# FrontEnd-rev1-superseded.net
KiCad netlist of a schematic drawn in Altium Designer
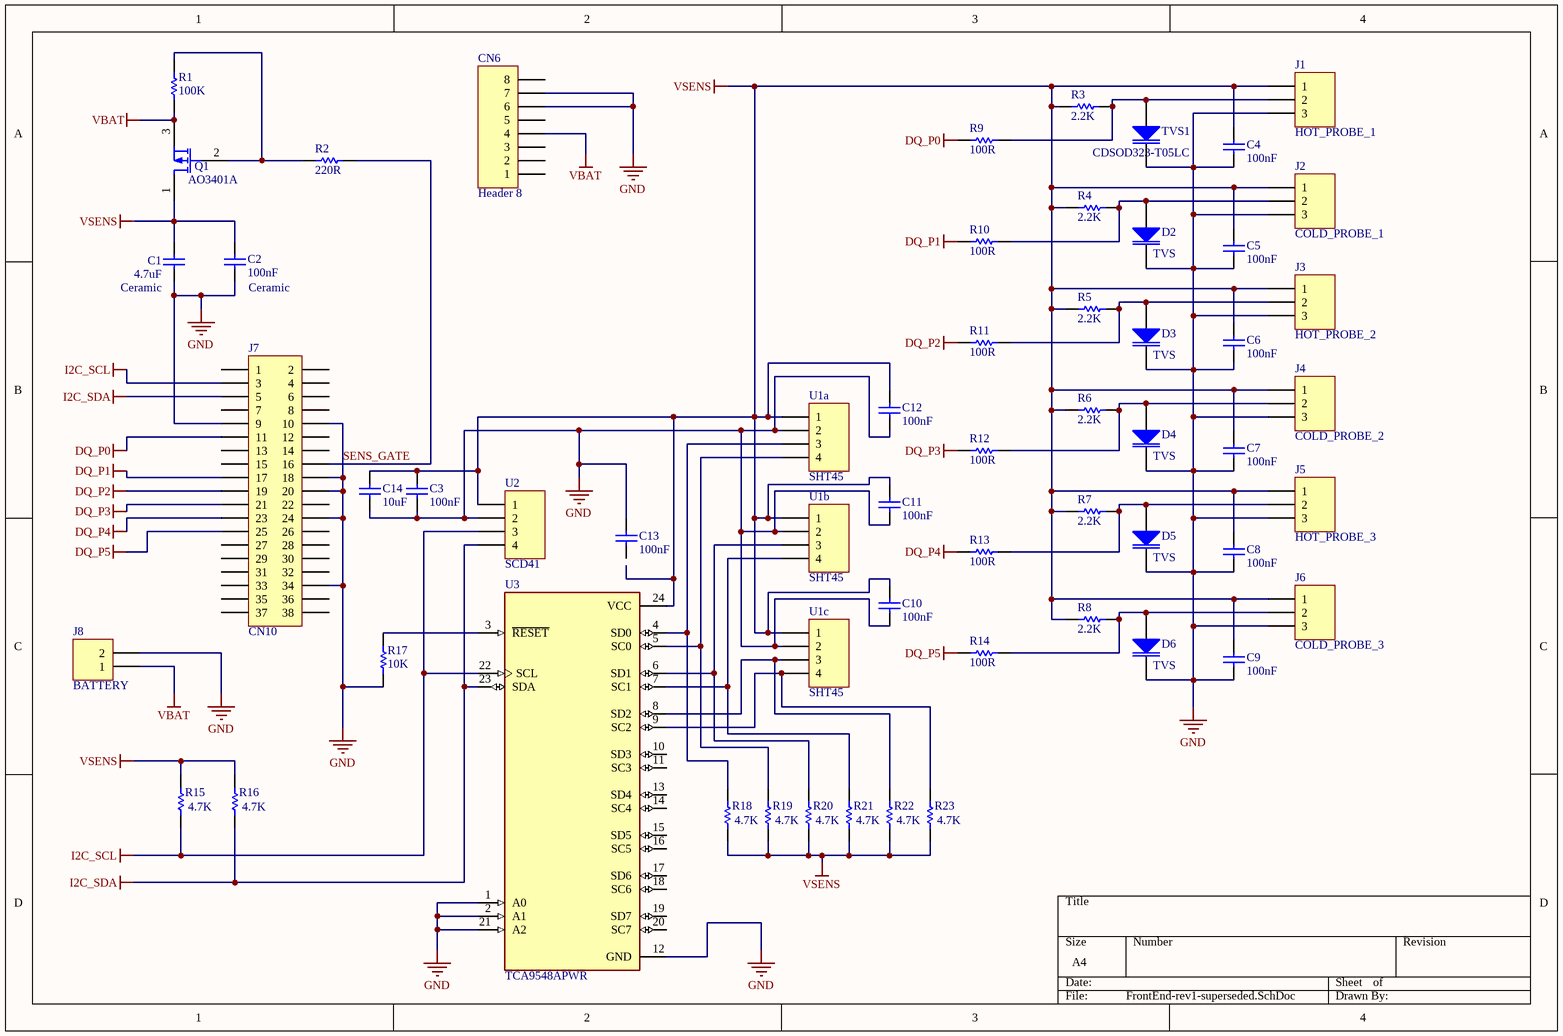
[diagram p0: FrontEnd-rev1-superseded.SchDoc]

(export (version "E")
  (design (tool "Eeschema 10.0.6"))
  (components
    (comp (ref "C1")
      (value "Ceramic")
      (footprint "RAD-0.3")
      (description "Capacitor")
      (fields (field (name "ALTIUM_VALUE") "4.7uF") (field (name "PUBLISHER") "Altium Limited"))
      (libsource (lib "Miscellaneous Devices") (part "Cap"))
    )
    (comp (ref "C2")
      (value "Ceramic")
      (footprint "RAD-0.3")
      (description "Capacitor")
      (fields (field (name "ALTIUM_VALUE") "100nF") (field (name "PUBLISHER") "Altium Limited"))
      (libsource (lib "Miscellaneous Devices") (part "Cap"))
    )
    (comp (ref "C3")
      (value "100nF")
      (footprint "RAD-0.3")
      (description "Capacitor")
      (fields (field (name "PUBLISHER") "Altium Limited"))
      (libsource (lib "Miscellaneous Devices") (part "Cap"))
    )
    (comp (ref "C4")
      (value "100nF")
      (footprint "RAD-0.3")
      (description "Capacitor")
      (fields (field (name "PUBLISHER") "Altium Limited"))
      (libsource (lib "Miscellaneous Devices") (part "Cap"))
    )
    (comp (ref "C5")
      (value "100nF")
      (footprint "RAD-0.3")
      (description "Capacitor")
      (fields (field (name "PUBLISHER") "Altium Limited"))
      (libsource (lib "Miscellaneous Devices") (part "Cap"))
    )
    (comp (ref "C6")
      (value "100nF")
      (footprint "RAD-0.3")
      (description "Capacitor")
      (fields (field (name "PUBLISHER") "Altium Limited"))
      (libsource (lib "Miscellaneous Devices") (part "Cap"))
    )
    (comp (ref "C7")
      (value "100nF")
      (footprint "RAD-0.3")
      (description "Capacitor")
      (fields (field (name "PUBLISHER") "Altium Limited"))
      (libsource (lib "Miscellaneous Devices") (part "Cap"))
    )
    (comp (ref "C8")
      (value "100nF")
      (footprint "RAD-0.3")
      (description "Capacitor")
      (fields (field (name "PUBLISHER") "Altium Limited"))
      (libsource (lib "Miscellaneous Devices") (part "Cap"))
    )
    (comp (ref "C9")
      (value "100nF")
      (footprint "RAD-0.3")
      (description "Capacitor")
      (fields (field (name "PUBLISHER") "Altium Limited"))
      (libsource (lib "Miscellaneous Devices") (part "Cap"))
    )
    (comp (ref "C10")
      (value "100nF")
      (footprint "RAD-0.3")
      (description "Capacitor")
      (fields (field (name "PUBLISHER") "Altium Limited"))
      (libsource (lib "Miscellaneous Devices") (part "Cap"))
    )
    (comp (ref "C11")
      (value "100nF")
      (footprint "RAD-0.3")
      (description "Capacitor")
      (fields (field (name "PUBLISHER") "Altium Limited"))
      (libsource (lib "Miscellaneous Devices") (part "Cap"))
    )
    (comp (ref "C12")
      (value "100nF")
      (footprint "RAD-0.3")
      (description "Capacitor")
      (fields (field (name "PUBLISHER") "Altium Limited"))
      (libsource (lib "Miscellaneous Devices") (part "Cap"))
    )
    (comp (ref "C13")
      (value "100nF")
      (footprint "RAD-0.3")
      (description "Capacitor")
      (fields (field (name "PUBLISHER") "Altium Limited"))
      (libsource (lib "Miscellaneous Devices") (part "Cap"))
    )
    (comp (ref "C14")
      (value "10uF")
      (footprint "RAD-0.3")
      (description "Capacitor")
      (fields (field (name "Comment") "100nF") (field (name "PUBLISHER") "Altium Limited"))
      (libsource (lib "Miscellaneous Devices") (part "Cap"))
    )
    (comp (ref "CN6")
      (value "Header 8")
      (footprint "HDR1X8")
      (description "Header, 8-Pin")
      (fields (field (name "PUBLISHER") "Altium Limited"))
      (libsource (lib "Miscellaneous Connectors") (part "Header 8"))
    )
    (comp (ref "D2")
      (value "TVS")
      (footprint "SOT23_N")
      (description "SOT23 Silicon Planar Variable Capacitance Diode")
      (fields (field (name "PUBLISHER") "Altium Limited"))
      (libsource (lib "Miscellaneous Devices") (part "Diode BBY40"))
    )
    (comp (ref "D3")
      (value "TVS")
      (footprint "SOT23_N")
      (description "SOT23 Silicon Planar Variable Capacitance Diode")
      (fields (field (name "PUBLISHER") "Altium Limited"))
      (libsource (lib "Miscellaneous Devices") (part "Diode BBY40"))
    )
    (comp (ref "D4")
      (value "TVS")
      (footprint "SOT23_N")
      (description "SOT23 Silicon Planar Variable Capacitance Diode")
      (fields (field (name "PUBLISHER") "Altium Limited"))
      (libsource (lib "Miscellaneous Devices") (part "Diode BBY40"))
    )
    (comp (ref "D5")
      (value "TVS")
      (footprint "SOT23_N")
      (description "SOT23 Silicon Planar Variable Capacitance Diode")
      (fields (field (name "PUBLISHER") "Altium Limited"))
      (libsource (lib "Miscellaneous Devices") (part "Diode BBY40"))
    )
    (comp (ref "D6")
      (value "TVS")
      (footprint "SOT23_N")
      (description "SOT23 Silicon Planar Variable Capacitance Diode")
      (fields (field (name "PUBLISHER") "Altium Limited"))
      (libsource (lib "Miscellaneous Devices") (part "Diode BBY40"))
    )
    (comp (ref "J1")
      (value "HOT_PROBE_1")
      (footprint "HDR1X3")
      (description "Header, 3-Pin")
      (fields (field (name "PUBLISHER") "Altium Limited"))
      (libsource (lib "Miscellaneous Connectors") (part "Header 3"))
    )
    (comp (ref "J2")
      (value "COLD_PROBE_1")
      (footprint "HDR1X3")
      (description "Header, 3-Pin")
      (fields (field (name "PUBLISHER") "Altium Limited"))
      (libsource (lib "Miscellaneous Connectors") (part "Header 3"))
    )
    (comp (ref "J3")
      (value "HOT_PROBE_2")
      (footprint "HDR1X3")
      (description "Header, 3-Pin")
      (fields (field (name "PUBLISHER") "Altium Limited"))
      (libsource (lib "Miscellaneous Connectors") (part "Header 3"))
    )
    (comp (ref "J4")
      (value "COLD_PROBE_2")
      (footprint "HDR1X3")
      (description "Header, 3-Pin")
      (fields (field (name "PUBLISHER") "Altium Limited"))
      (libsource (lib "Miscellaneous Connectors") (part "Header 3"))
    )
    (comp (ref "J5")
      (value "HOT_PROBE_3")
      (footprint "HDR1X3")
      (description "Header, 3-Pin")
      (fields (field (name "PUBLISHER") "Altium Limited"))
      (libsource (lib "Miscellaneous Connectors") (part "Header 3"))
    )
    (comp (ref "J6")
      (value "COLD_PROBE_3")
      (footprint "HDR1X3")
      (description "Header, 3-Pin")
      (fields (field (name "PUBLISHER") "Altium Limited"))
      (libsource (lib "Miscellaneous Connectors") (part "Header 3"))
    )
    (comp (ref "J7")
      (value "CN10")
      (footprint "HDR2X19")
      (description "Header, 19-Pin, Dual row")
      (fields (field (name "PUBLISHER") "Altium Limited"))
      (libsource (lib "Miscellaneous Connectors") (part "Header 19X2"))
    )
    (comp (ref "J8")
      (value "BATTERY")
      (footprint "HDR1X2")
      (description "Header, 2-Pin")
      (fields (field (name "PUBLISHER") "Altium Limited"))
      (libsource (lib "Miscellaneous Connectors") (part "Header 2"))
    )
    (comp (ref "Q1")
      (value "AO3401A")
      (footprint "E3")
      (description "P-Channel MOSFET")
      (fields (field (name "PUBLISHER") "Altium Limited"))
      (libsource (lib "Miscellaneous Devices") (part "MOSFET-P"))
    )
    (comp (ref "R1")
      (value "100K")
      (footprint "AXIAL-0.3")
      (description "Resistor")
      (fields (field (name "PUBLISHER") "Altium Limited"))
      (libsource (lib "Miscellaneous Devices") (part "Res1"))
    )
    (comp (ref "R2")
      (value "220R")
      (footprint "AXIAL-0.3")
      (description "Resistor")
      (fields (field (name "PUBLISHER") "Altium Limited"))
      (libsource (lib "Miscellaneous Devices") (part "Res1"))
    )
    (comp (ref "R3")
      (value "2.2K")
      (footprint "AXIAL-0.3")
      (description "Resistor")
      (fields (field (name "Comment") "pullup") (field (name "PUBLISHER") "Altium Limited"))
      (libsource (lib "Miscellaneous Devices") (part "Res1"))
    )
    (comp (ref "R4")
      (value "2.2K")
      (footprint "AXIAL-0.3")
      (description "Resistor")
      (fields (field (name "Comment") "pullup") (field (name "PUBLISHER") "Altium Limited"))
      (libsource (lib "Miscellaneous Devices") (part "Res1"))
    )
    (comp (ref "R5")
      (value "2.2K")
      (footprint "AXIAL-0.3")
      (description "Resistor")
      (fields (field (name "Comment") "pullup") (field (name "PUBLISHER") "Altium Limited"))
      (libsource (lib "Miscellaneous Devices") (part "Res1"))
    )
    (comp (ref "R6")
      (value "2.2K")
      (footprint "AXIAL-0.3")
      (description "Resistor")
      (fields (field (name "Comment") "pullup") (field (name "PUBLISHER") "Altium Limited"))
      (libsource (lib "Miscellaneous Devices") (part "Res1"))
    )
    (comp (ref "R7")
      (value "2.2K")
      (footprint "AXIAL-0.3")
      (description "Resistor")
      (fields (field (name "Comment") "pullup") (field (name "PUBLISHER") "Altium Limited"))
      (libsource (lib "Miscellaneous Devices") (part "Res1"))
    )
    (comp (ref "R8")
      (value "2.2K")
      (footprint "AXIAL-0.3")
      (description "Resistor")
      (fields (field (name "Comment") "pullup") (field (name "PUBLISHER") "Altium Limited"))
      (libsource (lib "Miscellaneous Devices") (part "Res1"))
    )
    (comp (ref "R9")
      (value "100R")
      (footprint "AXIAL-0.3")
      (description "Resistor")
      (fields (field (name "PUBLISHER") "Altium Limited"))
      (libsource (lib "Miscellaneous Devices") (part "Res1"))
    )
    (comp (ref "R10")
      (value "100R")
      (footprint "AXIAL-0.3")
      (description "Resistor")
      (fields (field (name "PUBLISHER") "Altium Limited"))
      (libsource (lib "Miscellaneous Devices") (part "Res1"))
    )
    (comp (ref "R11")
      (value "100R")
      (footprint "AXIAL-0.3")
      (description "Resistor")
      (fields (field (name "PUBLISHER") "Altium Limited"))
      (libsource (lib "Miscellaneous Devices") (part "Res1"))
    )
    (comp (ref "R12")
      (value "100R")
      (footprint "AXIAL-0.3")
      (description "Resistor")
      (fields (field (name "PUBLISHER") "Altium Limited"))
      (libsource (lib "Miscellaneous Devices") (part "Res1"))
    )
    (comp (ref "R13")
      (value "100R")
      (footprint "AXIAL-0.3")
      (description "Resistor")
      (fields (field (name "PUBLISHER") "Altium Limited"))
      (libsource (lib "Miscellaneous Devices") (part "Res1"))
    )
    (comp (ref "R14")
      (value "100R")
      (footprint "AXIAL-0.3")
      (description "Resistor")
      (fields (field (name "PUBLISHER") "Altium Limited"))
      (libsource (lib "Miscellaneous Devices") (part "Res1"))
    )
    (comp (ref "R15")
      (value "4.7K")
      (footprint "AXIAL-0.3")
      (description "Resistor")
      (fields (field (name "Comment") "pullup") (field (name "PUBLISHER") "Altium Limited"))
      (libsource (lib "Miscellaneous Devices") (part "Res1"))
    )
    (comp (ref "R16")
      (value "4.7K")
      (footprint "AXIAL-0.3")
      (description "Resistor")
      (fields (field (name "Comment") "pullup") (field (name "PUBLISHER") "Altium Limited"))
      (libsource (lib "Miscellaneous Devices") (part "Res1"))
    )
    (comp (ref "R17")
      (value "10K")
      (footprint "AXIAL-0.3")
      (description "Resistor")
      (fields (field (name "Comment") "220R") (field (name "PUBLISHER") "Altium Limited"))
      (libsource (lib "Miscellaneous Devices") (part "Res1"))
    )
    (comp (ref "R18")
      (value "4.7K")
      (footprint "AXIAL-0.3")
      (description "Resistor")
      (fields (field (name "Comment") "pullup") (field (name "PUBLISHER") "Altium Limited"))
      (libsource (lib "Miscellaneous Devices") (part "Res1"))
    )
    (comp (ref "R19")
      (value "4.7K")
      (footprint "AXIAL-0.3")
      (description "Resistor")
      (fields (field (name "Comment") "pullup") (field (name "PUBLISHER") "Altium Limited"))
      (libsource (lib "Miscellaneous Devices") (part "Res1"))
    )
    (comp (ref "R20")
      (value "4.7K")
      (footprint "AXIAL-0.3")
      (description "Resistor")
      (fields (field (name "Comment") "pullup") (field (name "PUBLISHER") "Altium Limited"))
      (libsource (lib "Miscellaneous Devices") (part "Res1"))
    )
    (comp (ref "R21")
      (value "4.7K")
      (footprint "AXIAL-0.3")
      (description "Resistor")
      (fields (field (name "Comment") "pullup") (field (name "PUBLISHER") "Altium Limited"))
      (libsource (lib "Miscellaneous Devices") (part "Res1"))
    )
    (comp (ref "R22")
      (value "4.7K")
      (footprint "AXIAL-0.3")
      (description "Resistor")
      (fields (field (name "Comment") "pullup") (field (name "PUBLISHER") "Altium Limited"))
      (libsource (lib "Miscellaneous Devices") (part "Res1"))
    )
    (comp (ref "R23")
      (value "4.7K")
      (footprint "AXIAL-0.3")
      (description "Resistor")
      (fields (field (name "Comment") "pullup") (field (name "PUBLISHER") "Altium Limited"))
      (libsource (lib "Miscellaneous Devices") (part "Res1"))
    )
    (comp (ref "TVS1")
      (value "CDSOD323-T05LC")
      (footprint "SOT23_N")
      (description "SOT23 Silicon Planar Variable Capacitance Diode")
      (fields (field (name "PUBLISHER") "Altium Limited"))
      (libsource (lib "Miscellaneous Devices") (part "Diode BBY40"))
    )
    (comp (ref "U1a")
      (value "SHT45")
      (footprint "HDR1X4")
      (description "Header, 4-Pin")
      (fields (field (name "PUBLISHER") "Altium Limited"))
      (libsource (lib "Miscellaneous Connectors") (part "Header 4"))
    )
    (comp (ref "U1b")
      (value "SHT45")
      (footprint "HDR1X4")
      (description "Header, 4-Pin")
      (fields (field (name "PUBLISHER") "Altium Limited"))
      (libsource (lib "Miscellaneous Connectors") (part "Header 4"))
    )
    (comp (ref "U1c")
      (value "SHT45")
      (footprint "HDR1X4")
      (description "Header, 4-Pin")
      (fields (field (name "PUBLISHER") "Altium Limited"))
      (libsource (lib "Miscellaneous Connectors") (part "Header 4"))
    )
    (comp (ref "U2")
      (value "SCD41")
      (footprint "HDR1X4")
      (description "Header, 4-Pin")
      (fields (field (name "PUBLISHER") "Altium Limited"))
      (libsource (lib "Miscellaneous Connectors") (part "Header 4"))
    )
    (comp (ref "U3")
      (value "TCA9548APWR")
      (footprint "SOP65P640X120-24N")
      (description "8-channel 1.65- to 5.5-V I2C/SMBus switch with reset & voltage translation")
      (fields (field (name "MF") "Texas Instruments"))
      (libsource (lib "TCA9548APWR") (part "TCA9548APWR"))
    )
  )
  (nets
    (net (code "1") (name "DQ_P0") (class "Default")
      (node (ref "J7") (pin "11") (pinfunction "11_11") (pintype "passive"))
      (node (ref "R9") (pin "1") (pinfunction "1_1") (pintype "passive"))
    )
    (net (code "2") (name "DQ_P1") (class "Default")
      (node (ref "J7") (pin "17") (pinfunction "17_17") (pintype "passive"))
      (node (ref "R10") (pin "1") (pinfunction "1_1") (pintype "passive"))
    )
    (net (code "3") (name "DQ_P2") (class "Default")
      (node (ref "J7") (pin "19") (pinfunction "19_19") (pintype "passive"))
      (node (ref "R11") (pin "1") (pinfunction "1_1") (pintype "passive"))
    )
    (net (code "4") (name "DQ_P3") (class "Default")
      (node (ref "J7") (pin "21") (pinfunction "21_21") (pintype "passive"))
      (node (ref "R12") (pin "1") (pinfunction "1_1") (pintype "passive"))
    )
    (net (code "5") (name "DQ_P4") (class "Default")
      (node (ref "J7") (pin "23") (pinfunction "23_23") (pintype "passive"))
      (node (ref "R13") (pin "1") (pinfunction "1_1") (pintype "passive"))
    )
    (net (code "6") (name "DQ_P5") (class "Default")
      (node (ref "J7") (pin "25") (pinfunction "25_25") (pintype "passive"))
      (node (ref "R14") (pin "1") (pinfunction "1_1") (pintype "passive"))
    )
    (net (code "7") (name "GND") (class "Default")
      (node (ref "C1") (pin "2") (pinfunction "2_2") (pintype "passive"))
      (node (ref "C10") (pin "2") (pinfunction "2_2") (pintype "passive"))
      (node (ref "C11") (pin "2") (pinfunction "2_2") (pintype "passive"))
      (node (ref "C12") (pin "2") (pinfunction "2_2") (pintype "passive"))
      (node (ref "C13") (pin "1") (pinfunction "1_1") (pintype "passive"))
      (node (ref "C14") (pin "2") (pinfunction "2_2") (pintype "passive"))
      (node (ref "C2") (pin "2") (pinfunction "2_2") (pintype "passive"))
      (node (ref "C3") (pin "2") (pinfunction "2_2") (pintype "passive"))
      (node (ref "C4") (pin "2") (pinfunction "2_2") (pintype "passive"))
      (node (ref "C5") (pin "2") (pinfunction "2_2") (pintype "passive"))
      (node (ref "C6") (pin "2") (pinfunction "2_2") (pintype "passive"))
      (node (ref "C7") (pin "2") (pinfunction "2_2") (pintype "passive"))
      (node (ref "C8") (pin "2") (pinfunction "2_2") (pintype "passive"))
      (node (ref "C9") (pin "2") (pinfunction "2_2") (pintype "passive"))
      (node (ref "CN6") (pin "6") (pinfunction "6_6") (pintype "passive"))
      (node (ref "CN6") (pin "7") (pinfunction "7_7") (pintype "passive"))
      (node (ref "D2") (pin "1") (pinfunction "K_1") (pintype "passive"))
      (node (ref "D3") (pin "1") (pinfunction "K_1") (pintype "passive"))
      (node (ref "D4") (pin "1") (pinfunction "K_1") (pintype "passive"))
      (node (ref "D5") (pin "1") (pinfunction "K_1") (pintype "passive"))
      (node (ref "D6") (pin "1") (pinfunction "K_1") (pintype "passive"))
      (node (ref "J1") (pin "3") (pinfunction "3_3") (pintype "passive"))
      (node (ref "J2") (pin "3") (pinfunction "3_3") (pintype "passive"))
      (node (ref "J3") (pin "3") (pinfunction "3_3") (pintype "passive"))
      (node (ref "J4") (pin "3") (pinfunction "3_3") (pintype "passive"))
      (node (ref "J5") (pin "3") (pinfunction "3_3") (pintype "passive"))
      (node (ref "J6") (pin "3") (pinfunction "3_3") (pintype "passive"))
      (node (ref "J7") (pin "10") (pinfunction "10_10") (pintype "passive"))
      (node (ref "J7") (pin "16") (pinfunction "16_16") (pintype "passive"))
      (node (ref "J7") (pin "18") (pinfunction "18_18") (pintype "passive"))
      (node (ref "J7") (pin "20") (pinfunction "20_20") (pintype "passive"))
      (node (ref "J7") (pin "24") (pinfunction "24_24") (pintype "passive"))
      (node (ref "J7") (pin "34") (pinfunction "34_34") (pintype "passive"))
      (node (ref "J7") (pin "9") (pinfunction "9_9") (pintype "passive"))
      (node (ref "J8") (pin "2") (pinfunction "2_2") (pintype "passive"))
      (node (ref "R17") (pin "2") (pinfunction "2_2") (pintype "passive"))
      (node (ref "R2") (pin "1") (pinfunction "1_1") (pintype "passive"))
      (node (ref "TVS1") (pin "1") (pinfunction "K_1") (pintype "passive"))
      (node (ref "U1a") (pin "2") (pinfunction "2_2") (pintype "passive"))
      (node (ref "U1b") (pin "2") (pinfunction "2_2") (pintype "passive"))
      (node (ref "U1c") (pin "2") (pinfunction "2_2") (pintype "passive"))
      (node (ref "U2") (pin "2") (pinfunction "2_2") (pintype "passive"))
      (node (ref "U3") (pin "1") (pinfunction "A0_1") (pintype "input"))
      (node (ref "U3") (pin "12") (pinfunction "GND_12") (pintype "power_in"))
      (node (ref "U3") (pin "2") (pinfunction "A1_2") (pintype "input"))
      (node (ref "U3") (pin "21") (pinfunction "A2_21") (pintype "input"))
    )
    (net (code "8") (name "I2C_SCL") (class "Default")
      (node (ref "J7") (pin "3") (pinfunction "3_3") (pintype "passive"))
      (node (ref "R15") (pin "1") (pinfunction "1_1") (pintype "passive"))
      (node (ref "U2") (pin "3") (pinfunction "3_3") (pintype "passive"))
      (node (ref "U3") (pin "22") (pinfunction "SCL_22") (pintype "input"))
    )
    (net (code "9") (name "I2C_SDA") (class "Default")
      (node (ref "J7") (pin "5") (pinfunction "5_5") (pintype "passive"))
      (node (ref "R16") (pin "1") (pinfunction "1_1") (pintype "passive"))
      (node (ref "U2") (pin "4") (pinfunction "4_4") (pintype "passive"))
      (node (ref "U3") (pin "23") (pinfunction "SDA_23") (pintype "bidirectional"))
    )
    (net (code "10") (name "Net-(D2-A)") (class "Default")
      (node (ref "D2") (pin "3") (pinfunction "A_3") (pintype "passive"))
      (node (ref "J2") (pin "2") (pinfunction "2_2") (pintype "passive"))
      (node (ref "R10") (pin "2") (pinfunction "2_2") (pintype "passive"))
      (node (ref "R4") (pin "1") (pinfunction "1_1") (pintype "passive"))
    )
    (net (code "11") (name "Net-(D3-A)") (class "Default")
      (node (ref "D3") (pin "3") (pinfunction "A_3") (pintype "passive"))
      (node (ref "J3") (pin "2") (pinfunction "2_2") (pintype "passive"))
      (node (ref "R11") (pin "2") (pinfunction "2_2") (pintype "passive"))
      (node (ref "R5") (pin "1") (pinfunction "1_1") (pintype "passive"))
    )
    (net (code "12") (name "Net-(D4-A)") (class "Default")
      (node (ref "D4") (pin "3") (pinfunction "A_3") (pintype "passive"))
      (node (ref "J4") (pin "2") (pinfunction "2_2") (pintype "passive"))
      (node (ref "R12") (pin "2") (pinfunction "2_2") (pintype "passive"))
      (node (ref "R6") (pin "1") (pinfunction "1_1") (pintype "passive"))
    )
    (net (code "13") (name "Net-(D5-A)") (class "Default")
      (node (ref "D5") (pin "3") (pinfunction "A_3") (pintype "passive"))
      (node (ref "J5") (pin "2") (pinfunction "2_2") (pintype "passive"))
      (node (ref "R13") (pin "2") (pinfunction "2_2") (pintype "passive"))
      (node (ref "R7") (pin "1") (pinfunction "1_1") (pintype "passive"))
    )
    (net (code "14") (name "Net-(D6-A)") (class "Default")
      (node (ref "D6") (pin "3") (pinfunction "A_3") (pintype "passive"))
      (node (ref "J6") (pin "2") (pinfunction "2_2") (pintype "passive"))
      (node (ref "R14") (pin "2") (pinfunction "2_2") (pintype "passive"))
      (node (ref "R8") (pin "1") (pinfunction "1_1") (pintype "passive"))
    )
    (net (code "15") (name "Net-(Q1-G)") (class "Default")
      (node (ref "Q1") (pin "2") (pinfunction "G_2") (pintype "passive"))
      (node (ref "R1") (pin "1") (pinfunction "1_1") (pintype "passive"))
      (node (ref "R2") (pin "2") (pinfunction "2_2") (pintype "passive"))
    )
    (net (code "16") (name "Net-(TVS1-A)") (class "Default")
      (node (ref "J1") (pin "2") (pinfunction "2_2") (pintype "passive"))
      (node (ref "R3") (pin "1") (pinfunction "1_1") (pintype "passive"))
      (node (ref "R9") (pin "2") (pinfunction "2_2") (pintype "passive"))
      (node (ref "TVS1") (pin "3") (pinfunction "A_3") (pintype "passive"))
    )
    (net (code "17") (name "Net-(U3-SC0)") (class "Default")
      (node (ref "R19") (pin "2") (pinfunction "2_2") (pintype "passive"))
      (node (ref "U1a") (pin "4") (pinfunction "4_4") (pintype "passive"))
      (node (ref "U3") (pin "5") (pinfunction "SC0_5") (pintype "bidirectional"))
    )
    (net (code "18") (name "Net-(U3-SC1)") (class "Default")
      (node (ref "R21") (pin "2") (pinfunction "2_2") (pintype "passive"))
      (node (ref "U1b") (pin "4") (pinfunction "4_4") (pintype "passive"))
      (node (ref "U3") (pin "7") (pinfunction "SC1_7") (pintype "bidirectional"))
    )
    (net (code "19") (name "Net-(U3-SC2)") (class "Default")
      (node (ref "R23") (pin "2") (pinfunction "2_2") (pintype "passive"))
      (node (ref "U1c") (pin "4") (pinfunction "4_4") (pintype "passive"))
      (node (ref "U3") (pin "9") (pinfunction "SC2_9") (pintype "bidirectional"))
    )
    (net (code "20") (name "Net-(U3-SD0)") (class "Default")
      (node (ref "R18") (pin "2") (pinfunction "2_2") (pintype "passive"))
      (node (ref "U1a") (pin "3") (pinfunction "3_3") (pintype "passive"))
      (node (ref "U3") (pin "4") (pinfunction "SD0_4") (pintype "bidirectional"))
    )
    (net (code "21") (name "Net-(U3-SD1)") (class "Default")
      (node (ref "R20") (pin "2") (pinfunction "2_2") (pintype "passive"))
      (node (ref "U1b") (pin "3") (pinfunction "3_3") (pintype "passive"))
      (node (ref "U3") (pin "6") (pinfunction "SD1_6") (pintype "bidirectional"))
    )
    (net (code "22") (name "Net-(U3-SD2)") (class "Default")
      (node (ref "R22") (pin "2") (pinfunction "2_2") (pintype "passive"))
      (node (ref "U1c") (pin "3") (pinfunction "3_3") (pintype "passive"))
      (node (ref "U3") (pin "8") (pinfunction "SD2_8") (pintype "bidirectional"))
    )
    (net (code "23") (name "Net-(U3-~{RESET})") (class "Default")
      (node (ref "R17") (pin "1") (pinfunction "1_1") (pintype "passive"))
      (node (ref "U3") (pin "3") (pinfunction "~{RESET}_3") (pintype "input"))
    )
    (net (code "24") (name "VBAT") (class "Default")
      (node (ref "CN6") (pin "4") (pinfunction "4_4") (pintype "passive"))
      (node (ref "J8") (pin "1") (pinfunction "1_1") (pintype "passive"))
      (node (ref "Q1") (pin "3") (pinfunction "S_3") (pintype "passive"))
      (node (ref "R1") (pin "2") (pinfunction "2_2") (pintype "passive"))
    )
    (net (code "25") (name "VSENS") (class "Default")
      (node (ref "C1") (pin "1") (pinfunction "1_1") (pintype "passive"))
      (node (ref "C10") (pin "1") (pinfunction "1_1") (pintype "passive"))
      (node (ref "C11") (pin "1") (pinfunction "1_1") (pintype "passive"))
      (node (ref "C12") (pin "1") (pinfunction "1_1") (pintype "passive"))
      (node (ref "C14") (pin "1") (pinfunction "1_1") (pintype "passive"))
      (node (ref "C2") (pin "1") (pinfunction "1_1") (pintype "passive"))
      (node (ref "C3") (pin "1") (pinfunction "1_1") (pintype "passive"))
      (node (ref "C4") (pin "1") (pinfunction "1_1") (pintype "passive"))
      (node (ref "C5") (pin "1") (pinfunction "1_1") (pintype "passive"))
      (node (ref "C6") (pin "1") (pinfunction "1_1") (pintype "passive"))
      (node (ref "C7") (pin "1") (pinfunction "1_1") (pintype "passive"))
      (node (ref "C8") (pin "1") (pinfunction "1_1") (pintype "passive"))
      (node (ref "C9") (pin "1") (pinfunction "1_1") (pintype "passive"))
      (node (ref "J1") (pin "1") (pinfunction "1_1") (pintype "passive"))
      (node (ref "J2") (pin "1") (pinfunction "1_1") (pintype "passive"))
      (node (ref "J3") (pin "1") (pinfunction "1_1") (pintype "passive"))
      (node (ref "J4") (pin "1") (pinfunction "1_1") (pintype "passive"))
      (node (ref "J5") (pin "1") (pinfunction "1_1") (pintype "passive"))
      (node (ref "J6") (pin "1") (pinfunction "1_1") (pintype "passive"))
      (node (ref "Q1") (pin "1") (pinfunction "D_1") (pintype "passive"))
      (node (ref "R15") (pin "2") (pinfunction "2_2") (pintype "passive"))
      (node (ref "R16") (pin "2") (pinfunction "2_2") (pintype "passive"))
      (node (ref "R18") (pin "1") (pinfunction "1_1") (pintype "passive"))
      (node (ref "R19") (pin "1") (pinfunction "1_1") (pintype "passive"))
      (node (ref "R20") (pin "1") (pinfunction "1_1") (pintype "passive"))
      (node (ref "R21") (pin "1") (pinfunction "1_1") (pintype "passive"))
      (node (ref "R22") (pin "1") (pinfunction "1_1") (pintype "passive"))
      (node (ref "R23") (pin "1") (pinfunction "1_1") (pintype "passive"))
      (node (ref "R3") (pin "2") (pinfunction "2_2") (pintype "passive"))
      (node (ref "R4") (pin "2") (pinfunction "2_2") (pintype "passive"))
      (node (ref "R5") (pin "2") (pinfunction "2_2") (pintype "passive"))
      (node (ref "R6") (pin "2") (pinfunction "2_2") (pintype "passive"))
      (node (ref "R7") (pin "2") (pinfunction "2_2") (pintype "passive"))
      (node (ref "R8") (pin "2") (pinfunction "2_2") (pintype "passive"))
      (node (ref "U1a") (pin "1") (pinfunction "1_1") (pintype "passive"))
      (node (ref "U1b") (pin "1") (pinfunction "1_1") (pintype "passive"))
      (node (ref "U1c") (pin "1") (pinfunction "1_1") (pintype "passive"))
      (node (ref "U2") (pin "1") (pinfunction "1_1") (pintype "passive"))
      (node (ref "U3") (pin "24") (pinfunction "VCC_24") (pintype "power_in"))
    )
    (net (code "26") (name "unconnected-(C13-Pad2)") (class "Default")
      (node (ref "C13") (pin "2") (pinfunction "2_2") (pintype "passive"))
    )
    (net (code "27") (name "unconnected-(CN6-Pad1)") (class "Default")
      (node (ref "CN6") (pin "1") (pinfunction "1_1") (pintype "passive"))
    )
    (net (code "28") (name "unconnected-(CN6-Pad2)") (class "Default")
      (node (ref "CN6") (pin "2") (pinfunction "2_2") (pintype "passive"))
    )
    (net (code "29") (name "unconnected-(CN6-Pad3)") (class "Default")
      (node (ref "CN6") (pin "3") (pinfunction "3_3") (pintype "passive"))
    )
    (net (code "30") (name "unconnected-(CN6-Pad5)") (class "Default")
      (node (ref "CN6") (pin "5") (pinfunction "5_5") (pintype "passive"))
    )
    (net (code "31") (name "unconnected-(CN6-Pad8)") (class "Default")
      (node (ref "CN6") (pin "8") (pinfunction "8_8") (pintype "passive"))
    )
    (net (code "32") (name "unconnected-(J7-Pad1)") (class "Default")
      (node (ref "J7") (pin "1") (pinfunction "1_1") (pintype "passive"))
    )
    (net (code "33") (name "unconnected-(J7-Pad2)") (class "Default")
      (node (ref "J7") (pin "2") (pinfunction "2_2") (pintype "passive"))
    )
    (net (code "34") (name "unconnected-(J7-Pad4)") (class "Default")
      (node (ref "J7") (pin "4") (pinfunction "4_4") (pintype "passive"))
    )
    (net (code "35") (name "unconnected-(J7-Pad6)") (class "Default")
      (node (ref "J7") (pin "6") (pinfunction "6_6") (pintype "passive"))
    )
    (net (code "36") (name "unconnected-(J7-Pad7)") (class "Default")
      (node (ref "J7") (pin "7") (pinfunction "7_7") (pintype "passive"))
    )
    (net (code "37") (name "unconnected-(J7-Pad8)") (class "Default")
      (node (ref "J7") (pin "8") (pinfunction "8_8") (pintype "passive"))
    )
    (net (code "38") (name "unconnected-(J7-Pad12)") (class "Default")
      (node (ref "J7") (pin "12") (pinfunction "12_12") (pintype "passive"))
    )
    (net (code "39") (name "unconnected-(J7-Pad13)") (class "Default")
      (node (ref "J7") (pin "13") (pinfunction "13_13") (pintype "passive"))
    )
    (net (code "40") (name "unconnected-(J7-Pad14)") (class "Default")
      (node (ref "J7") (pin "14") (pinfunction "14_14") (pintype "passive"))
    )
    (net (code "41") (name "unconnected-(J7-Pad15)") (class "Default")
      (node (ref "J7") (pin "15") (pinfunction "15_15") (pintype "passive"))
    )
    (net (code "42") (name "unconnected-(J7-Pad22)") (class "Default")
      (node (ref "J7") (pin "22") (pinfunction "22_22") (pintype "passive"))
    )
    (net (code "43") (name "unconnected-(J7-Pad26)") (class "Default")
      (node (ref "J7") (pin "26") (pinfunction "26_26") (pintype "passive"))
    )
    (net (code "44") (name "unconnected-(J7-Pad27)") (class "Default")
      (node (ref "J7") (pin "27") (pinfunction "27_27") (pintype "passive"))
    )
    (net (code "45") (name "unconnected-(J7-Pad28)") (class "Default")
      (node (ref "J7") (pin "28") (pinfunction "28_28") (pintype "passive"))
    )
    (net (code "46") (name "unconnected-(J7-Pad29)") (class "Default")
      (node (ref "J7") (pin "29") (pinfunction "29_29") (pintype "passive"))
    )
    (net (code "47") (name "unconnected-(J7-Pad30)") (class "Default")
      (node (ref "J7") (pin "30") (pinfunction "30_30") (pintype "passive"))
    )
    (net (code "48") (name "unconnected-(J7-Pad31)") (class "Default")
      (node (ref "J7") (pin "31") (pinfunction "31_31") (pintype "passive"))
    )
    (net (code "49") (name "unconnected-(J7-Pad32)") (class "Default")
      (node (ref "J7") (pin "32") (pinfunction "32_32") (pintype "passive"))
    )
    (net (code "50") (name "unconnected-(J7-Pad33)") (class "Default")
      (node (ref "J7") (pin "33") (pinfunction "33_33") (pintype "passive"))
    )
    (net (code "51") (name "unconnected-(J7-Pad35)") (class "Default")
      (node (ref "J7") (pin "35") (pinfunction "35_35") (pintype "passive"))
    )
    (net (code "52") (name "unconnected-(J7-Pad36)") (class "Default")
      (node (ref "J7") (pin "36") (pinfunction "36_36") (pintype "passive"))
    )
    (net (code "53") (name "unconnected-(J7-Pad37)") (class "Default")
      (node (ref "J7") (pin "37") (pinfunction "37_37") (pintype "passive"))
    )
    (net (code "54") (name "unconnected-(J7-Pad38)") (class "Default")
      (node (ref "J7") (pin "38") (pinfunction "38_38") (pintype "passive"))
    )
    (net (code "55") (name "unconnected-(U3-SC3-Pad11)") (class "Default")
      (node (ref "U3") (pin "11") (pinfunction "SC3_11") (pintype "bidirectional"))
    )
    (net (code "56") (name "unconnected-(U3-SC4-Pad14)") (class "Default")
      (node (ref "U3") (pin "14") (pinfunction "SC4_14") (pintype "bidirectional"))
    )
    (net (code "57") (name "unconnected-(U3-SC5-Pad16)") (class "Default")
      (node (ref "U3") (pin "16") (pinfunction "SC5_16") (pintype "bidirectional"))
    )
    (net (code "58") (name "unconnected-(U3-SC6-Pad18)") (class "Default")
      (node (ref "U3") (pin "18") (pinfunction "SC6_18") (pintype "bidirectional"))
    )
    (net (code "59") (name "unconnected-(U3-SC7-Pad20)") (class "Default")
      (node (ref "U3") (pin "20") (pinfunction "SC7_20") (pintype "bidirectional"))
    )
    (net (code "60") (name "unconnected-(U3-SD3-Pad10)") (class "Default")
      (node (ref "U3") (pin "10") (pinfunction "SD3_10") (pintype "bidirectional"))
    )
    (net (code "61") (name "unconnected-(U3-SD4-Pad13)") (class "Default")
      (node (ref "U3") (pin "13") (pinfunction "SD4_13") (pintype "bidirectional"))
    )
    (net (code "62") (name "unconnected-(U3-SD5-Pad15)") (class "Default")
      (node (ref "U3") (pin "15") (pinfunction "SD5_15") (pintype "bidirectional"))
    )
    (net (code "63") (name "unconnected-(U3-SD6-Pad17)") (class "Default")
      (node (ref "U3") (pin "17") (pinfunction "SD6_17") (pintype "bidirectional"))
    )
    (net (code "64") (name "unconnected-(U3-SD7-Pad19)") (class "Default")
      (node (ref "U3") (pin "19") (pinfunction "SD7_19") (pintype "bidirectional"))
    )
  )
)
